# nanang_sensor.net
KiCad netlist of a schematic drawn in EAGLE
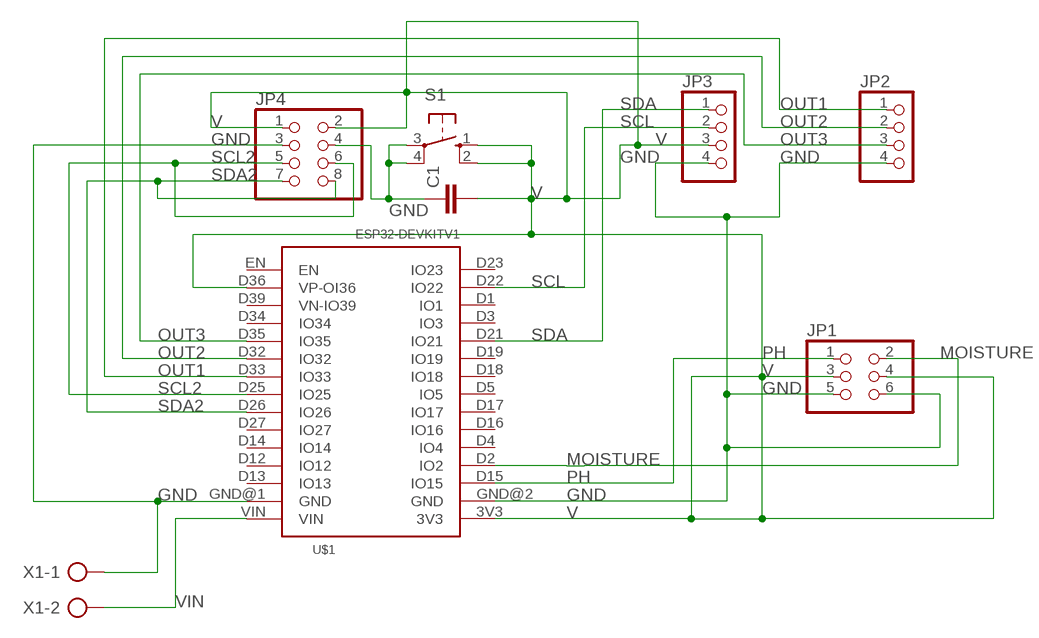
[diagram p0: schematic, sheet 1]

(export (version "E")
  (design (tool "Eeschema 10.0.6"))
  (components
    (comp (ref "C1")
      (value "C-EU050-030X075")
      (footprint "eagle-import:C050-030X075")
      (libsource (lib "eagle-import") (part "C-EU050-030X075"))
    )
    (comp (ref "JP1")
      (value "PINHD-2X3")
      (footprint "eagle-import:2X03")
      (libsource (lib "eagle-import") (part "PINHD-2X3"))
    )
    (comp (ref "JP2")
      (value "PINHD-1X4")
      (footprint "eagle-import:1X04")
      (libsource (lib "eagle-import") (part "PINHD-1X4"))
    )
    (comp (ref "JP3")
      (value "PINHD-1X4")
      (footprint "eagle-import:1X04")
      (libsource (lib "eagle-import") (part "PINHD-1X4"))
    )
    (comp (ref "JP4")
      (value "PINHD-2X4")
      (footprint "eagle-import:2X04")
      (libsource (lib "eagle-import") (part "PINHD-2X4"))
    )
    (comp (ref "S1")
      (value "10-XX")
      (footprint "eagle-import:B3F-10XX")
      (fields (field (name "MPN") "B3F-1000"))
      (libsource (lib "eagle-import") (part "10-XX"))
    )
    (comp (ref "U$1")
      (value "ESP32DEVKITV1")
      (footprint "eagle-import:ESP32-DEVKITV1")
      (libsource (lib "eagle-import") (part "ESP32DEVKITV1"))
    )
    (comp (ref "X1")
      (value "AK300/2")
      (footprint "eagle-import:AK300_2")
      (libsource (lib "eagle-import") (part "AK300/2"))
    )
  )
  (nets
    (net (code "1") (name "/GND") (class "Default")
      (node (ref "C1") (pin "1") (pinfunction "1_1") (pintype "passive"))
      (node (ref "JP1") (pin "5") (pinfunction "5_5") (pintype "passive"))
      (node (ref "JP1") (pin "6") (pinfunction "6_6") (pintype "passive"))
      (node (ref "JP2") (pin "4") (pinfunction "4_4") (pintype "passive"))
      (node (ref "JP3") (pin "4") (pinfunction "4_4") (pintype "passive"))
      (node (ref "JP4") (pin "3") (pinfunction "3_3") (pintype "passive"))
      (node (ref "JP4") (pin "4") (pinfunction "4_4") (pintype "passive"))
      (node (ref "S1") (pin "3") (pinfunction "P_3") (pintype "passive"))
      (node (ref "S1") (pin "4") (pinfunction "P1_4") (pintype "passive"))
      (node (ref "U$1") (pin "GND@1") (pinfunction "GND_GND@1") (pintype "bidirectional"))
      (node (ref "U$1") (pin "GND@2") (pinfunction "GND_GND@2") (pintype "bidirectional"))
      (node (ref "X1") (pin "1") (pinfunction "KL_1") (pintype "passive"))
    )
    (net (code "2") (name "/MOISTURE") (class "Default")
      (node (ref "JP1") (pin "2") (pinfunction "2_2") (pintype "passive"))
      (node (ref "U$1") (pin "D2") (pinfunction "IO2_D2") (pintype "bidirectional"))
    )
    (net (code "3") (name "/OUT1") (class "Default")
      (node (ref "JP2") (pin "1") (pinfunction "1_1") (pintype "passive"))
      (node (ref "U$1") (pin "D33") (pinfunction "IO33_D33") (pintype "bidirectional"))
    )
    (net (code "4") (name "/OUT2") (class "Default")
      (node (ref "JP2") (pin "2") (pinfunction "2_2") (pintype "passive"))
      (node (ref "U$1") (pin "D32") (pinfunction "IO32_D32") (pintype "bidirectional"))
    )
    (net (code "5") (name "/OUT3") (class "Default")
      (node (ref "JP2") (pin "3") (pinfunction "3_3") (pintype "passive"))
      (node (ref "U$1") (pin "D35") (pinfunction "IO35_D35") (pintype "bidirectional"))
    )
    (net (code "6") (name "/PH") (class "Default")
      (node (ref "JP1") (pin "1") (pinfunction "1_1") (pintype "passive"))
      (node (ref "U$1") (pin "D15") (pinfunction "IO15_D15") (pintype "bidirectional"))
    )
    (net (code "7") (name "/SCL") (class "Default")
      (node (ref "JP3") (pin "2") (pinfunction "2_2") (pintype "passive"))
      (node (ref "U$1") (pin "D22") (pinfunction "IO22_D22") (pintype "bidirectional"))
    )
    (net (code "8") (name "/SCL2") (class "Default")
      (node (ref "JP4") (pin "5") (pinfunction "5_5") (pintype "passive"))
      (node (ref "JP4") (pin "6") (pinfunction "6_6") (pintype "passive"))
      (node (ref "U$1") (pin "D25") (pinfunction "IO25_D25") (pintype "bidirectional"))
    )
    (net (code "9") (name "/SDA") (class "Default")
      (node (ref "JP3") (pin "1") (pinfunction "1_1") (pintype "passive"))
      (node (ref "U$1") (pin "D21") (pinfunction "IO21_D21") (pintype "bidirectional"))
    )
    (net (code "10") (name "/SDA2") (class "Default")
      (node (ref "JP4") (pin "7") (pinfunction "7_7") (pintype "passive"))
      (node (ref "JP4") (pin "8") (pinfunction "8_8") (pintype "passive"))
      (node (ref "U$1") (pin "D26") (pinfunction "IO26_D26") (pintype "bidirectional"))
    )
    (net (code "11") (name "/V") (class "Default")
      (node (ref "C1") (pin "2") (pinfunction "2_2") (pintype "passive"))
      (node (ref "JP1") (pin "3") (pinfunction "3_3") (pintype "passive"))
      (node (ref "JP1") (pin "4") (pinfunction "4_4") (pintype "passive"))
      (node (ref "JP3") (pin "3") (pinfunction "3_3") (pintype "passive"))
      (node (ref "JP4") (pin "1") (pinfunction "1_1") (pintype "passive"))
      (node (ref "JP4") (pin "2") (pinfunction "2_2") (pintype "passive"))
      (node (ref "S1") (pin "1") (pinfunction "S_1") (pintype "passive"))
      (node (ref "S1") (pin "2") (pinfunction "S1_2") (pintype "passive"))
      (node (ref "U$1") (pin "3V3") (pinfunction "3V3_3V3") (pintype "bidirectional"))
      (node (ref "U$1") (pin "D36") (pinfunction "VP-OI36_D36") (pintype "bidirectional"))
    )
    (net (code "12") (name "/VIN") (class "Default")
      (node (ref "U$1") (pin "VIN") (pinfunction "VIN_VIN") (pintype "bidirectional"))
      (node (ref "X1") (pin "2") (pinfunction "KL_2") (pintype "passive"))
    )
    (net (code "13") (name "unconnected-(U$1-IO1-PadD1)") (class "Default")
      (node (ref "U$1") (pin "D1") (pinfunction "IO1_D1") (pintype "bidirectional"))
    )
    (net (code "14") (name "unconnected-(U$1-IO3-PadD3)") (class "Default")
      (node (ref "U$1") (pin "D3") (pinfunction "IO3_D3") (pintype "bidirectional"))
    )
    (net (code "15") (name "unconnected-(U$1-IO4-PadD4)") (class "Default")
      (node (ref "U$1") (pin "D4") (pinfunction "IO4_D4") (pintype "bidirectional"))
    )
    (net (code "16") (name "unconnected-(U$1-IO5-PadD5)") (class "Default")
      (node (ref "U$1") (pin "D5") (pinfunction "IO5_D5") (pintype "bidirectional"))
    )
    (net (code "17") (name "unconnected-(U$1-IO12-PadD12)") (class "Default")
      (node (ref "U$1") (pin "D12") (pinfunction "IO12_D12") (pintype "bidirectional"))
    )
    (net (code "18") (name "unconnected-(U$1-IO13-PadD13)") (class "Default")
      (node (ref "U$1") (pin "D13") (pinfunction "IO13_D13") (pintype "bidirectional"))
    )
    (net (code "19") (name "unconnected-(U$1-IO14-PadD14)") (class "Default")
      (node (ref "U$1") (pin "D14") (pinfunction "IO14_D14") (pintype "bidirectional"))
    )
    (net (code "20") (name "unconnected-(U$1-IO16-PadD16)") (class "Default")
      (node (ref "U$1") (pin "D16") (pinfunction "IO16_D16") (pintype "bidirectional"))
    )
    (net (code "21") (name "unconnected-(U$1-IO17-PadD17)") (class "Default")
      (node (ref "U$1") (pin "D17") (pinfunction "IO17_D17") (pintype "bidirectional"))
    )
    (net (code "22") (name "unconnected-(U$1-IO18-PadD18)") (class "Default")
      (node (ref "U$1") (pin "D18") (pinfunction "IO18_D18") (pintype "bidirectional"))
    )
    (net (code "23") (name "unconnected-(U$1-IO19-PadD19)") (class "Default")
      (node (ref "U$1") (pin "D19") (pinfunction "IO19_D19") (pintype "bidirectional"))
    )
    (net (code "24") (name "unconnected-(U$1-IO23-PadD23)") (class "Default")
      (node (ref "U$1") (pin "D23") (pinfunction "IO23_D23") (pintype "bidirectional"))
    )
    (net (code "25") (name "unconnected-(U$1-IO27-PadD27)") (class "Default")
      (node (ref "U$1") (pin "D27") (pinfunction "IO27_D27") (pintype "bidirectional"))
    )
    (net (code "26") (name "unconnected-(U$1-IO34-PadD34)") (class "Default")
      (node (ref "U$1") (pin "D34") (pinfunction "IO34_D34") (pintype "bidirectional"))
    )
    (net (code "27") (name "unconnected-(U$1-PadEN)") (class "Default")
      (node (ref "U$1") (pin "EN") (pinfunction "EN_EN") (pintype "bidirectional"))
    )
    (net (code "28") (name "unconnected-(U$1-VN-IO39-PadD39)") (class "Default")
      (node (ref "U$1") (pin "D39") (pinfunction "VN-IO39_D39") (pintype "bidirectional"))
    )
  )
)
